# MOSFET_motor_driver.net
KiCad netlist of a schematic drawn in EAGLE
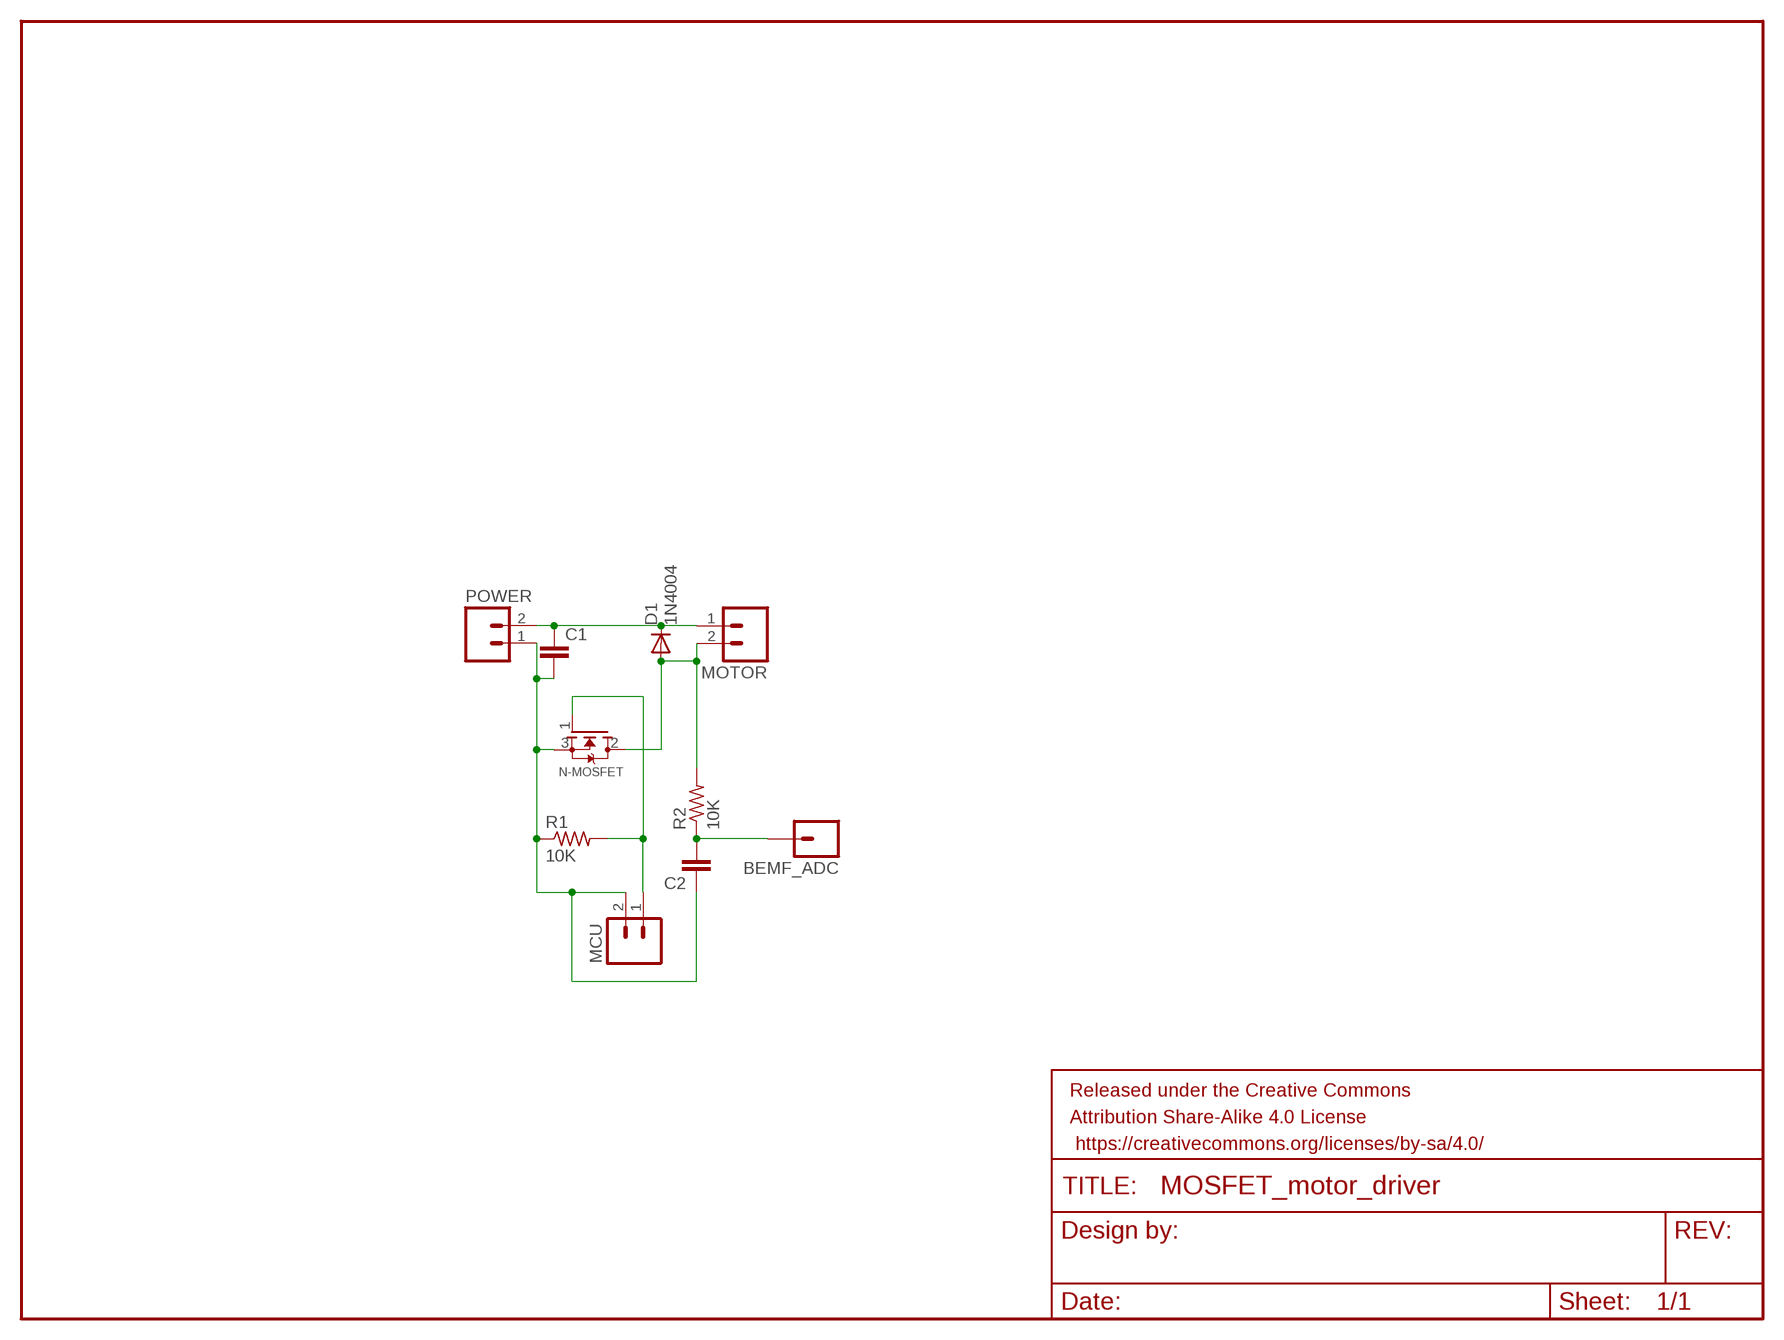
[diagram p0: schematic, sheet 1]

(export (version "E")
  (design (tool "Eeschema 10.0.6"))
  (components
    (comp (ref "BEMF_ADC")
      (value "M01PTH")
      (footprint "eagle-import:1X01")
      (libsource (lib "eagle-import") (part "M01PTH"))
    )
    (comp (ref "C1")
      (value "CAPPTH")
      (footprint "eagle-import:CAP-PTH-SMALL")
      (libsource (lib "eagle-import") (part "CAPPTH"))
    )
    (comp (ref "C2")
      (value "CAPPTH")
      (footprint "eagle-import:CAP-PTH-SMALL")
      (libsource (lib "eagle-import") (part "CAPPTH"))
    )
    (comp (ref "D1")
      (value "1N4004")
      (footprint "eagle-import:DO41-10")
      (libsource (lib "eagle-import") (part "1N4004"))
    )
    (comp (ref "FRAME1")
      (value "FRAME-LETTER")
      (footprint "eagle-import:CREATIVE_COMMONS")
      (libsource (lib "eagle-import") (part "FRAME-LETTER"))
    )
    (comp (ref "MCU")
      (value "M02PTH")
      (footprint "eagle-import:1X02")
      (libsource (lib "eagle-import") (part "M02PTH"))
    )
    (comp (ref "MOTOR")
      (value "M02PTH")
      (footprint "eagle-import:1X02")
      (libsource (lib "eagle-import") (part "M02PTH"))
    )
    (comp (ref "N-MOSFET")
      (value "MOSFET-NGDS_TO220V")
      (footprint "eagle-import:TO220V")
      (libsource (lib "eagle-import") (part "MOSFET-NGDS_TO220V"))
    )
    (comp (ref "POWER")
      (value "M02PTH")
      (footprint "eagle-import:1X02")
      (libsource (lib "eagle-import") (part "M02PTH"))
    )
    (comp (ref "R1")
      (value "10K")
      (footprint "eagle-import:0207_10")
      (libsource (lib "eagle-import") (part "R-US_0207/10"))
    )
    (comp (ref "R2")
      (value "10K")
      (footprint "eagle-import:0207_10")
      (libsource (lib "eagle-import") (part "R-US_0207/10"))
    )
  )
  (nets
    (net (code "1") (name "Net-(BEMF_ADC-Pad1)") (class "Default")
      (node (ref "BEMF_ADC") (pin "1") (pinfunction "1_1") (pintype "passive"))
      (node (ref "C2") (pin "2") (pinfunction "2_2") (pintype "passive"))
      (node (ref "R2") (pin "1") (pinfunction "1_1") (pintype "passive"))
    )
    (net (code "2") (name "Net-(C1-Pad1)") (class "Default")
      (node (ref "C1") (pin "1") (pinfunction "1_1") (pintype "passive"))
      (node (ref "D1") (pin "C") (pinfunction "C_C") (pintype "passive"))
      (node (ref "MOTOR") (pin "1") (pinfunction "1_1") (pintype "passive"))
      (node (ref "POWER") (pin "2") (pinfunction "2_2") (pintype "passive"))
    )
    (net (code "3") (name "Net-(N-MOSFET-D)") (class "Default")
      (node (ref "D1") (pin "A") (pinfunction "A_A") (pintype "passive"))
      (node (ref "MOTOR") (pin "2") (pinfunction "2_2") (pintype "passive"))
      (node (ref "N-MOSFET") (pin "2") (pinfunction "D_2") (pintype "bidirectional"))
      (node (ref "R2") (pin "2") (pinfunction "2_2") (pintype "passive"))
    )
    (net (code "4") (name "Net-(N-MOSFET-G)") (class "Default")
      (node (ref "MCU") (pin "1") (pinfunction "1_1") (pintype "passive"))
      (node (ref "N-MOSFET") (pin "1") (pinfunction "G_1") (pintype "bidirectional"))
      (node (ref "R1") (pin "2") (pinfunction "2_2") (pintype "passive"))
    )
    (net (code "5") (name "Net-(N-MOSFET-S)") (class "Default")
      (node (ref "C1") (pin "2") (pinfunction "2_2") (pintype "passive"))
      (node (ref "C2") (pin "1") (pinfunction "1_1") (pintype "passive"))
      (node (ref "MCU") (pin "2") (pinfunction "2_2") (pintype "passive"))
      (node (ref "N-MOSFET") (pin "3") (pinfunction "S_3") (pintype "bidirectional"))
      (node (ref "POWER") (pin "1") (pinfunction "1_1") (pintype "passive"))
      (node (ref "R1") (pin "1") (pinfunction "1_1") (pintype "passive"))
    )
  )
)
